# MCU_Hydro.net
KiCad netlist of a schematic drawn in Altium Designer
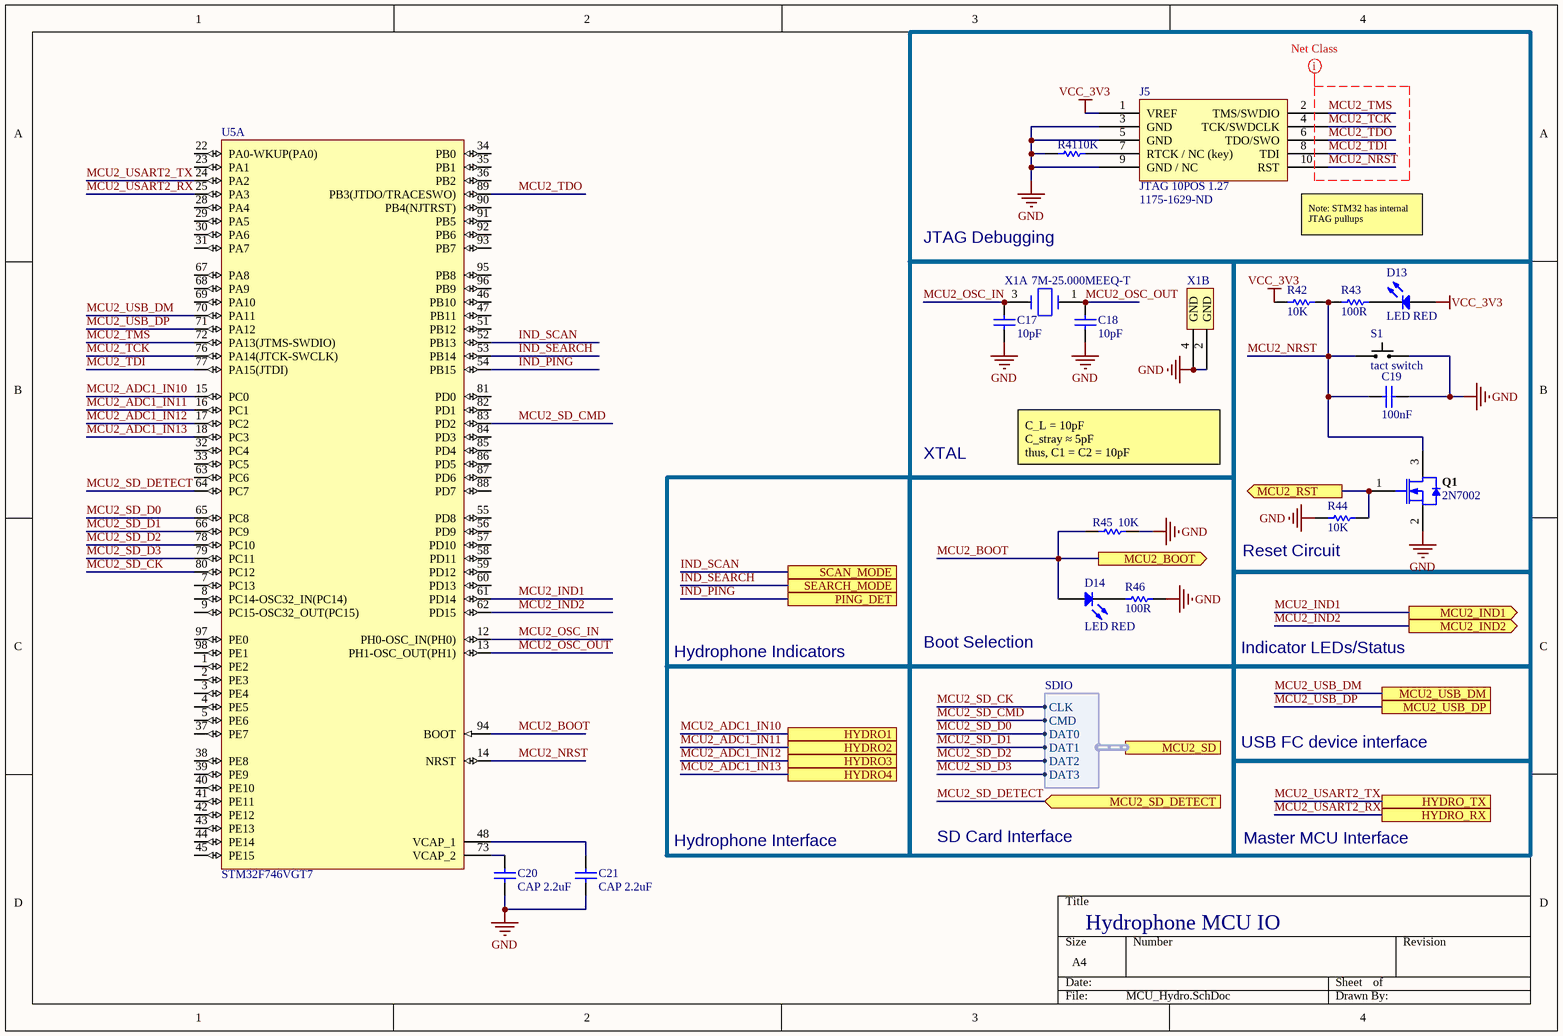
[diagram p0: MCU_Hydro.SchDoc]

(export (version "E")
  (design (tool "Eeschema 10.0.6"))
  (components
    (comp (ref "C17")
      (value "10pF")
      (footprint "CAPC0603(1608)100_N")
      (description "CAP 10pF 25V ±1% 0603 (1608 Metric) Thickness 1mm SMD")
      (fields (field (name "TOLERANCE") "Â±1%"))
      (libsource (lib "Altium Content Vault") (part "CAP"))
    )
    (comp (ref "C18")
      (value "10pF")
      (footprint "CAPC0603(1608)100_N")
      (description "CAP 10pF 25V ±1% 0603 (1608 Metric) Thickness 1mm SMD")
      (fields (field (name "TOLERANCE") "Â±1%"))
      (libsource (lib "Altium Content Vault") (part "CAP"))
    )
    (comp (ref "C19")
      (value "100nF")
      (footprint "CAPC0603(1608)100_N")
      (description "CAP 100nF 10V ±10% 0603 (1608 Metric) Thickness 1mm SMD")
      (fields (field (name "TOLERANCE") "Â±10%"))
      (libsource (lib "Altium Content Vault") (part "CAP"))
    )
    (comp (ref "C20")
      (value "CAP 2.2uF")
      (footprint "CAPC0603(1608)100_N")
      (description "CAP 2.2uF 10V ±10% 0603 (1608 Metric) Thickness 1mm SMD")
      (fields (field (name "TOLERANCE") "Â±10%"))
      (libsource (lib "Altium Content Vault") (part "CAP"))
    )
    (comp (ref "C21")
      (value "CAP 2.2uF")
      (footprint "CAPC0603(1608)100_N")
      (description "CAP 2.2uF 10V ±10% 0603 (1608 Metric) Thickness 1mm SMD")
      (fields (field (name "TOLERANCE") "Â±10%"))
      (libsource (lib "Altium Content Vault") (part "CAP"))
    )
    (comp (ref "D13")
      (value "LED RED")
      (footprint "LED_0805")
      (description "led")
      (fields
        (field (name "MANUFACTURER") "Lite-On Inc.")
        (field (name "MANUFACTURER PART NUMBER") "LTST-C171KRKT")
      )
      (libsource (lib "CMR_Miscellaneous_Devices") (part "LED0"))
    )
    (comp (ref "D14")
      (value "LED RED")
      (footprint "LED_0805")
      (description "led")
      (fields
        (field (name "MANUFACTURER") "Lite-On Inc.")
        (field (name "MANUFACTURER PART NUMBER") "LTST-C171KRKT")
      )
      (libsource (lib "CMR_Miscellaneous_Devices") (part "LED0"))
    )
    (comp (ref "J5")
      (value "JTAG 10POS 1.27")
      (footprint "5x2 JTAG SMD")
      (fields (field (name "SUPPLIER PART NUMBER 1") "1175-1629-ND"))
      (libsource (lib "CMR_Miscellaneous_Devices") (part "jtag 10pos mini"))
    )
    (comp (ref "Q1")
      (value "2N7002")
      (footprint "INF-PG-SOT23_M")
      (fields (field (name "MANUFACTURER") "Infineon"))
      (libsource (lib "Altium Content Vault") (part "INF-NDMOS-GSD-3"))
    )
    (comp (ref "R41")
      (value "10K")
      (footprint "RESC0603(1608)_N")
      (description "10K 0.1W 5% 0603 (1608 Metric)  SMD")
      (fields (field (name "TOLERANCE") "5 %") (field (name "POWER") "0.1 W"))
      (libsource (lib "Altium Content Vault") (part "RES"))
    )
    (comp (ref "R42")
      (value "10K")
      (footprint "RESC0603(1608)_N")
      (description "10K 0.1W 5% 0603 (1608 Metric)  SMD")
      (fields (field (name "TOLERANCE") "5 %") (field (name "POWER") "0.1 W"))
      (libsource (lib "Altium Content Vault") (part "RES"))
    )
    (comp (ref "R43")
      (value "100R")
      (footprint "RESC0603(1608)_N")
      (description "100R 0.1W 5% 0603 (1608 Metric)  SMD")
      (fields (field (name "TOLERANCE") "5 %") (field (name "POWER") "0.1 W"))
      (libsource (lib "Altium Content Vault") (part "RES"))
    )
    (comp (ref "R44")
      (value "10K")
      (footprint "RESC0603(1608)_N")
      (description "10K 0.1W 5% 0603 (1608 Metric)  SMD")
      (fields (field (name "TOLERANCE") "5 %") (field (name "POWER") "0.1 W"))
      (libsource (lib "Altium Content Vault") (part "RES"))
    )
    (comp (ref "R45")
      (value "10K")
      (footprint "RESC0603(1608)_N")
      (description "10K 0.1W 5% 0603 (1608 Metric)  SMD")
      (fields (field (name "TOLERANCE") "5 %") (field (name "POWER") "0.1 W"))
      (libsource (lib "Altium Content Vault") (part "RES"))
    )
    (comp (ref "R46")
      (value "100R")
      (footprint "RESC0603(1608)_N")
      (description "100R 0.1W 5% 0603 (1608 Metric)  SMD")
      (fields (field (name "TOLERANCE") "5 %") (field (name "POWER") "0.1 W"))
      (libsource (lib "Altium Content Vault") (part "RES"))
    )
    (comp (ref "S1")
      (value "tact switch")
      (footprint "EVP-AA202K")
      (description "EVP-AA Momentary Switch SPST-NO")
      (fields (field (name "PART NUMBER") "EVP-AA202K"))
      (libsource (lib "CMR_Miscellaneous_Devices") (part "EVP-AA Switch"))
    )
    (comp (ref "U5")
      (value "STM32F746VGT7")
      (footprint "STM-LQFP100_L")
      (libsource (lib "Altium Content Vault") (part "MC-ARM-STM32F7X6-LQFP100"))
    )
    (comp (ref "X1")
      (value "7M-25.000MEEQ-T")
      (footprint "OSCSC320X250X100N")
      (description "CRYSTAL 25.0000MHZ 10PF SMD")
      (fields (field (name "TOLERANCE") "10ppm"))
      (libsource (lib "CMR_Miscellaneous_Devices") (part "7M-25.000MEEQ-T"))
    )
  )
  (nets
    (net (code "2") (name "/IND_PING") (class "Default")
      (node (ref "U5") (pin "54") (pinfunction "PB15_54") (pintype "bidirectional"))
    )
    (net (code "3") (name "/IND_SCAN") (class "Default")
      (node (ref "U5") (pin "52") (pinfunction "PB13_52") (pintype "bidirectional"))
    )
    (net (code "4") (name "/IND_SEARCH") (class "Default")
      (node (ref "U5") (pin "53") (pinfunction "PB14_53") (pintype "bidirectional"))
    )
    (net (code "5") (name "/MCU2_ADC1_IN10") (class "Default")
      (node (ref "U5") (pin "15") (pinfunction "PC0_15") (pintype "bidirectional"))
    )
    (net (code "6") (name "/MCU2_ADC1_IN11") (class "Default")
      (node (ref "U5") (pin "16") (pinfunction "PC1_16") (pintype "bidirectional"))
    )
    (net (code "7") (name "/MCU2_ADC1_IN12") (class "Default")
      (node (ref "U5") (pin "17") (pinfunction "PC2_17") (pintype "bidirectional"))
    )
    (net (code "8") (name "/MCU2_ADC1_IN13") (class "Default")
      (node (ref "U5") (pin "18") (pinfunction "PC3_18") (pintype "bidirectional"))
    )
    (net (code "9") (name "/MCU2_BOOT") (class "Default")
      (node (ref "D14") (pin "2") (pinfunction "A_2") (pintype "passive"))
      (node (ref "R45") (pin "1") (pinfunction "1_1") (pintype "passive"))
      (node (ref "U5") (pin "94") (pinfunction "BOOT_94") (pintype "input"))
    )
    (net (code "10") (name "/MCU2_IND1") (class "Default")
      (node (ref "U5") (pin "61") (pinfunction "PD14_61") (pintype "bidirectional"))
    )
    (net (code "11") (name "/MCU2_IND2") (class "Default")
      (node (ref "U5") (pin "62") (pinfunction "PD15_62") (pintype "bidirectional"))
    )
    (net (code "12") (name "/MCU2_NRST") (class "Default")
      (node (ref "C19") (pin "2") (pinfunction "2_2") (pintype "passive"))
      (node (ref "J5") (pin "10") (pinfunction "RST_10") (pintype "passive"))
      (node (ref "Q1") (pin "3") (pinfunction "DRAIN_3") (pintype "passive"))
      (node (ref "R42") (pin "1") (pinfunction "1_1") (pintype "passive"))
      (node (ref "R43") (pin "2") (pinfunction "2_2") (pintype "passive"))
      (node (ref "S1") (pin "1") (pinfunction "1_1") (pintype "passive"))
      (node (ref "U5") (pin "14") (pinfunction "NRST_14") (pintype "bidirectional"))
    )
    (net (code "13") (name "/MCU2_OSC_IN") (class "Default")
      (node (ref "C17") (pin "2") (pinfunction "2_2") (pintype "passive"))
      (node (ref "U5") (pin "12") (pinfunction "PH0-OSC_IN(PH0)_12") (pintype "bidirectional"))
      (node (ref "X1") (pin "3") (pintype "passive"))
    )
    (net (code "14") (name "/MCU2_OSC_OUT") (class "Default")
      (node (ref "C18") (pin "2") (pinfunction "2_2") (pintype "passive"))
      (node (ref "U5") (pin "13") (pinfunction "PH1-OSC_OUT(PH1)_13") (pintype "bidirectional"))
      (node (ref "X1") (pin "1") (pinfunction "11_1") (pintype "passive"))
    )
    (net (code "15") (name "/MCU2_RST") (class "Default")
      (node (ref "Q1") (pin "1") (pinfunction "GATE_1") (pintype "passive"))
      (node (ref "R44") (pin "1") (pinfunction "1_1") (pintype "passive"))
    )
    (net (code "16") (name "/MCU2_SD_CK") (class "Default")
      (node (ref "U5") (pin "80") (pinfunction "PC12_80") (pintype "bidirectional"))
    )
    (net (code "17") (name "/MCU2_SD_CMD") (class "Default")
      (node (ref "U5") (pin "83") (pinfunction "PD2_83") (pintype "bidirectional"))
    )
    (net (code "18") (name "/MCU2_SD_D0") (class "Default")
      (node (ref "U5") (pin "65") (pinfunction "PC8_65") (pintype "bidirectional"))
    )
    (net (code "19") (name "/MCU2_SD_D1") (class "Default")
      (node (ref "U5") (pin "66") (pinfunction "PC9_66") (pintype "bidirectional"))
    )
    (net (code "20") (name "/MCU2_SD_D2") (class "Default")
      (node (ref "U5") (pin "78") (pinfunction "PC10_78") (pintype "bidirectional"))
    )
    (net (code "21") (name "/MCU2_SD_D3") (class "Default")
      (node (ref "U5") (pin "79") (pinfunction "PC11_79") (pintype "bidirectional"))
    )
    (net (code "22") (name "/MCU2_SD_DETECT") (class "Default")
      (node (ref "U5") (pin "64") (pinfunction "PC7_64") (pintype "bidirectional"))
    )
    (net (code "23") (name "/MCU2_TCK") (class "Default")
      (node (ref "J5") (pin "4") (pinfunction "TCK/SWDCLK_4") (pintype "passive"))
      (node (ref "U5") (pin "76") (pinfunction "PA14(JTCK-SWCLK)_76") (pintype "bidirectional"))
    )
    (net (code "24") (name "/MCU2_TDI") (class "Default")
      (node (ref "J5") (pin "8") (pinfunction "TDI_8") (pintype "passive"))
      (node (ref "U5") (pin "77") (pinfunction "PA15(JTDI)_77") (pintype "bidirectional"))
    )
    (net (code "25") (name "/MCU2_TDO") (class "Default")
      (node (ref "J5") (pin "6") (pinfunction "TDO/SWO_6") (pintype "passive"))
      (node (ref "U5") (pin "89") (pinfunction "PB3(JTDO/TRACESWO)_89") (pintype "bidirectional"))
    )
    (net (code "26") (name "/MCU2_TMS") (class "Default")
      (node (ref "J5") (pin "2") (pinfunction "TMS/SWDIO_2") (pintype "passive"))
      (node (ref "U5") (pin "72") (pinfunction "PA13(JTMS-SWDIO)_72") (pintype "bidirectional"))
    )
    (net (code "27") (name "/MCU2_USART2_RX") (class "Default")
      (node (ref "U5") (pin "25") (pinfunction "PA3_25") (pintype "bidirectional"))
    )
    (net (code "28") (name "/MCU2_USART2_TX") (class "Default")
      (node (ref "U5") (pin "24") (pinfunction "PA2_24") (pintype "bidirectional"))
    )
    (net (code "29") (name "/MCU2_USB_DM") (class "Default")
      (node (ref "U5") (pin "70") (pinfunction "PA11_70") (pintype "bidirectional"))
    )
    (net (code "30") (name "/MCU2_USB_DP") (class "Default")
      (node (ref "U5") (pin "71") (pinfunction "PA12_71") (pintype "bidirectional"))
    )
    (net (code "32") (name "GND") (class "Default")
      (node (ref "C17") (pin "1") (pinfunction "1_1") (pintype "passive"))
      (node (ref "C18") (pin "1") (pinfunction "1_1") (pintype "passive"))
      (node (ref "C19") (pin "1") (pinfunction "1_1") (pintype "passive"))
      (node (ref "C20") (pin "1") (pinfunction "1_1") (pintype "passive"))
      (node (ref "C21") (pin "1") (pinfunction "1_1") (pintype "passive"))
      (node (ref "J5") (pin "3") (pinfunction "GND_3") (pintype "passive"))
      (node (ref "J5") (pin "5") (pinfunction "GND_5") (pintype "passive"))
      (node (ref "J5") (pin "9") (pinfunction "GND_/_NC_9") (pintype "passive"))
      (node (ref "Q1") (pin "2") (pinfunction "SOURCE_2") (pintype "passive"))
      (node (ref "R41") (pin "1") (pinfunction "1_1") (pintype "passive"))
      (node (ref "R44") (pin "2") (pinfunction "2_2") (pintype "passive"))
      (node (ref "R45") (pin "2") (pinfunction "2_2") (pintype "passive"))
      (node (ref "R46") (pin "2") (pinfunction "2_2") (pintype "passive"))
      (node (ref "S1") (pin "2") (pinfunction "2_2") (pintype "passive"))
      (node (ref "X1") (pin "2") (pinfunction "GND_2") (pintype "passive"))
      (node (ref "X1") (pin "4") (pinfunction "GND_4") (pintype "passive"))
    )
    (net (code "33") (name "Net-(D13-K)") (class "Default")
      (node (ref "D13") (pin "1") (pinfunction "K_1") (pintype "passive"))
      (node (ref "R43") (pin "1") (pinfunction "1_1") (pintype "passive"))
    )
    (net (code "34") (name "Net-(D14-K)") (class "Default")
      (node (ref "D14") (pin "1") (pinfunction "K_1") (pintype "passive"))
      (node (ref "R46") (pin "1") (pinfunction "1_1") (pintype "passive"))
    )
    (net (code "35") (name "Net-(J5-RTCK_{slash}_NC_(key))") (class "Default")
      (node (ref "J5") (pin "7") (pinfunction "RTCK_/_NC_(key)_7") (pintype "passive"))
      (node (ref "R41") (pin "2") (pinfunction "2_2") (pintype "passive"))
    )
    (net (code "36") (name "Net-(U5A-VCAP_1)") (class "Default")
      (node (ref "C21") (pin "2") (pinfunction "2_2") (pintype "passive"))
      (node (ref "U5") (pin "48") (pinfunction "VCAP_1_48") (pintype "passive"))
    )
    (net (code "37") (name "Net-(U5A-VCAP_2)") (class "Default")
      (node (ref "C20") (pin "2") (pinfunction "2_2") (pintype "passive"))
      (node (ref "U5") (pin "73") (pinfunction "VCAP_2_73") (pintype "passive"))
    )
    (net (code "38") (name "VCC_3V3") (class "Default")
      (node (ref "D13") (pin "2") (pinfunction "A_2") (pintype "passive"))
      (node (ref "J5") (pin "1") (pinfunction "VREF_1") (pintype "passive"))
      (node (ref "R42") (pin "2") (pinfunction "2_2") (pintype "passive"))
    )
    (net (code "39") (name "unconnected-(U5A-PA0-WKUP(PA0)-Pad22)") (class "Default")
      (node (ref "U5") (pin "22") (pinfunction "PA0-WKUP(PA0)_22") (pintype "bidirectional"))
    )
    (net (code "40") (name "unconnected-(U5A-PA1-Pad23)") (class "Default")
      (node (ref "U5") (pin "23") (pinfunction "PA1_23") (pintype "bidirectional"))
    )
    (net (code "41") (name "unconnected-(U5A-PA4-Pad28)") (class "Default")
      (node (ref "U5") (pin "28") (pinfunction "PA4_28") (pintype "bidirectional"))
    )
    (net (code "42") (name "unconnected-(U5A-PA5-Pad29)") (class "Default")
      (node (ref "U5") (pin "29") (pinfunction "PA5_29") (pintype "bidirectional"))
    )
    (net (code "43") (name "unconnected-(U5A-PA6-Pad30)") (class "Default")
      (node (ref "U5") (pin "30") (pinfunction "PA6_30") (pintype "bidirectional"))
    )
    (net (code "44") (name "unconnected-(U5A-PA7-Pad31)") (class "Default")
      (node (ref "U5") (pin "31") (pinfunction "PA7_31") (pintype "bidirectional"))
    )
    (net (code "45") (name "unconnected-(U5A-PA8-Pad67)") (class "Default")
      (node (ref "U5") (pin "67") (pinfunction "PA8_67") (pintype "bidirectional"))
    )
    (net (code "46") (name "unconnected-(U5A-PA9-Pad68)") (class "Default")
      (node (ref "U5") (pin "68") (pinfunction "PA9_68") (pintype "bidirectional"))
    )
    (net (code "47") (name "unconnected-(U5A-PA10-Pad69)") (class "Default")
      (node (ref "U5") (pin "69") (pinfunction "PA10_69") (pintype "bidirectional"))
    )
    (net (code "48") (name "unconnected-(U5A-PB0-Pad34)") (class "Default")
      (node (ref "U5") (pin "34") (pinfunction "PB0_34") (pintype "bidirectional"))
    )
    (net (code "49") (name "unconnected-(U5A-PB1-Pad35)") (class "Default")
      (node (ref "U5") (pin "35") (pinfunction "PB1_35") (pintype "bidirectional"))
    )
    (net (code "50") (name "unconnected-(U5A-PB2-Pad36)") (class "Default")
      (node (ref "U5") (pin "36") (pinfunction "PB2_36") (pintype "bidirectional"))
    )
    (net (code "51") (name "unconnected-(U5A-PB4(NJTRST)-Pad90)") (class "Default")
      (node (ref "U5") (pin "90") (pinfunction "PB4(NJTRST)_90") (pintype "bidirectional"))
    )
    (net (code "52") (name "unconnected-(U5A-PB5-Pad91)") (class "Default")
      (node (ref "U5") (pin "91") (pinfunction "PB5_91") (pintype "bidirectional"))
    )
    (net (code "53") (name "unconnected-(U5A-PB6-Pad92)") (class "Default")
      (node (ref "U5") (pin "92") (pinfunction "PB6_92") (pintype "bidirectional"))
    )
    (net (code "54") (name "unconnected-(U5A-PB7-Pad93)") (class "Default")
      (node (ref "U5") (pin "93") (pinfunction "PB7_93") (pintype "bidirectional"))
    )
    (net (code "55") (name "unconnected-(U5A-PB8-Pad95)") (class "Default")
      (node (ref "U5") (pin "95") (pinfunction "PB8_95") (pintype "bidirectional"))
    )
    (net (code "56") (name "unconnected-(U5A-PB9-Pad96)") (class "Default")
      (node (ref "U5") (pin "96") (pinfunction "PB9_96") (pintype "bidirectional"))
    )
    (net (code "57") (name "unconnected-(U5A-PB10-Pad46)") (class "Default")
      (node (ref "U5") (pin "46") (pinfunction "PB10_46") (pintype "bidirectional"))
    )
    (net (code "58") (name "unconnected-(U5A-PB11-Pad47)") (class "Default")
      (node (ref "U5") (pin "47") (pinfunction "PB11_47") (pintype "bidirectional"))
    )
    (net (code "59") (name "unconnected-(U5A-PB12-Pad51)") (class "Default")
      (node (ref "U5") (pin "51") (pinfunction "PB12_51") (pintype "bidirectional"))
    )
    (net (code "60") (name "unconnected-(U5A-PC4-Pad32)") (class "Default")
      (node (ref "U5") (pin "32") (pinfunction "PC4_32") (pintype "bidirectional"))
    )
    (net (code "61") (name "unconnected-(U5A-PC5-Pad33)") (class "Default")
      (node (ref "U5") (pin "33") (pinfunction "PC5_33") (pintype "bidirectional"))
    )
    (net (code "62") (name "unconnected-(U5A-PC6-Pad63)") (class "Default")
      (node (ref "U5") (pin "63") (pinfunction "PC6_63") (pintype "bidirectional"))
    )
    (net (code "63") (name "unconnected-(U5A-PC13-Pad7)") (class "Default")
      (node (ref "U5") (pin "7") (pinfunction "PC13_7") (pintype "bidirectional"))
    )
    (net (code "64") (name "unconnected-(U5A-PC14-OSC32_IN(PC14)-Pad8)") (class "Default")
      (node (ref "U5") (pin "8") (pinfunction "PC14-OSC32_IN(PC14)_8") (pintype "bidirectional"))
    )
    (net (code "65") (name "unconnected-(U5A-PC15-OSC32_OUT(PC15)-Pad9)") (class "Default")
      (node (ref "U5") (pin "9") (pinfunction "PC15-OSC32_OUT(PC15)_9") (pintype "bidirectional"))
    )
    (net (code "66") (name "unconnected-(U5A-PD0-Pad81)") (class "Default")
      (node (ref "U5") (pin "81") (pinfunction "PD0_81") (pintype "bidirectional"))
    )
    (net (code "67") (name "unconnected-(U5A-PD1-Pad82)") (class "Default")
      (node (ref "U5") (pin "82") (pinfunction "PD1_82") (pintype "bidirectional"))
    )
    (net (code "68") (name "unconnected-(U5A-PD3-Pad84)") (class "Default")
      (node (ref "U5") (pin "84") (pinfunction "PD3_84") (pintype "bidirectional"))
    )
    (net (code "69") (name "unconnected-(U5A-PD4-Pad85)") (class "Default")
      (node (ref "U5") (pin "85") (pinfunction "PD4_85") (pintype "bidirectional"))
    )
    (net (code "70") (name "unconnected-(U5A-PD5-Pad86)") (class "Default")
      (node (ref "U5") (pin "86") (pinfunction "PD5_86") (pintype "bidirectional"))
    )
    (net (code "71") (name "unconnected-(U5A-PD6-Pad87)") (class "Default")
      (node (ref "U5") (pin "87") (pinfunction "PD6_87") (pintype "bidirectional"))
    )
    (net (code "72") (name "unconnected-(U5A-PD7-Pad88)") (class "Default")
      (node (ref "U5") (pin "88") (pinfunction "PD7_88") (pintype "bidirectional"))
    )
    (net (code "73") (name "unconnected-(U5A-PD8-Pad55)") (class "Default")
      (node (ref "U5") (pin "55") (pinfunction "PD8_55") (pintype "bidirectional"))
    )
    (net (code "74") (name "unconnected-(U5A-PD9-Pad56)") (class "Default")
      (node (ref "U5") (pin "56") (pinfunction "PD9_56") (pintype "bidirectional"))
    )
    (net (code "75") (name "unconnected-(U5A-PD10-Pad57)") (class "Default")
      (node (ref "U5") (pin "57") (pinfunction "PD10_57") (pintype "bidirectional"))
    )
    (net (code "76") (name "unconnected-(U5A-PD11-Pad58)") (class "Default")
      (node (ref "U5") (pin "58") (pinfunction "PD11_58") (pintype "bidirectional"))
    )
    (net (code "77") (name "unconnected-(U5A-PD12-Pad59)") (class "Default")
      (node (ref "U5") (pin "59") (pinfunction "PD12_59") (pintype "bidirectional"))
    )
    (net (code "78") (name "unconnected-(U5A-PD13-Pad60)") (class "Default")
      (node (ref "U5") (pin "60") (pinfunction "PD13_60") (pintype "bidirectional"))
    )
    (net (code "79") (name "unconnected-(U5A-PE0-Pad97)") (class "Default")
      (node (ref "U5") (pin "97") (pinfunction "PE0_97") (pintype "bidirectional"))
    )
    (net (code "80") (name "unconnected-(U5A-PE1-Pad98)") (class "Default")
      (node (ref "U5") (pin "98") (pinfunction "PE1_98") (pintype "bidirectional"))
    )
    (net (code "81") (name "unconnected-(U5A-PE2-Pad1)") (class "Default")
      (node (ref "U5") (pin "1") (pinfunction "PE2_1") (pintype "bidirectional"))
    )
    (net (code "82") (name "unconnected-(U5A-PE3-Pad2)") (class "Default")
      (node (ref "U5") (pin "2") (pinfunction "PE3_2") (pintype "bidirectional"))
    )
    (net (code "83") (name "unconnected-(U5A-PE4-Pad3)") (class "Default")
      (node (ref "U5") (pin "3") (pinfunction "PE4_3") (pintype "bidirectional"))
    )
    (net (code "84") (name "unconnected-(U5A-PE5-Pad4)") (class "Default")
      (node (ref "U5") (pin "4") (pinfunction "PE5_4") (pintype "bidirectional"))
    )
    (net (code "85") (name "unconnected-(U5A-PE6-Pad5)") (class "Default")
      (node (ref "U5") (pin "5") (pinfunction "PE6_5") (pintype "bidirectional"))
    )
    (net (code "86") (name "unconnected-(U5A-PE7-Pad37)") (class "Default")
      (node (ref "U5") (pin "37") (pinfunction "PE7_37") (pintype "bidirectional"))
    )
    (net (code "87") (name "unconnected-(U5A-PE8-Pad38)") (class "Default")
      (node (ref "U5") (pin "38") (pinfunction "PE8_38") (pintype "bidirectional"))
    )
    (net (code "88") (name "unconnected-(U5A-PE9-Pad39)") (class "Default")
      (node (ref "U5") (pin "39") (pinfunction "PE9_39") (pintype "bidirectional"))
    )
    (net (code "89") (name "unconnected-(U5A-PE10-Pad40)") (class "Default")
      (node (ref "U5") (pin "40") (pinfunction "PE10_40") (pintype "bidirectional"))
    )
    (net (code "90") (name "unconnected-(U5A-PE11-Pad41)") (class "Default")
      (node (ref "U5") (pin "41") (pinfunction "PE11_41") (pintype "bidirectional"))
    )
    (net (code "91") (name "unconnected-(U5A-PE12-Pad42)") (class "Default")
      (node (ref "U5") (pin "42") (pinfunction "PE12_42") (pintype "bidirectional"))
    )
    (net (code "92") (name "unconnected-(U5A-PE13-Pad43)") (class "Default")
      (node (ref "U5") (pin "43") (pinfunction "PE13_43") (pintype "bidirectional"))
    )
    (net (code "93") (name "unconnected-(U5A-PE14-Pad44)") (class "Default")
      (node (ref "U5") (pin "44") (pinfunction "PE14_44") (pintype "bidirectional"))
    )
    (net (code "94") (name "unconnected-(U5A-PE15-Pad45)") (class "Default")
      (node (ref "U5") (pin "45") (pinfunction "PE15_45") (pintype "bidirectional"))
    )
  )
)
